# mic-preamp-stereo5.net
KiCad netlist of a schematic drawn in EAGLE
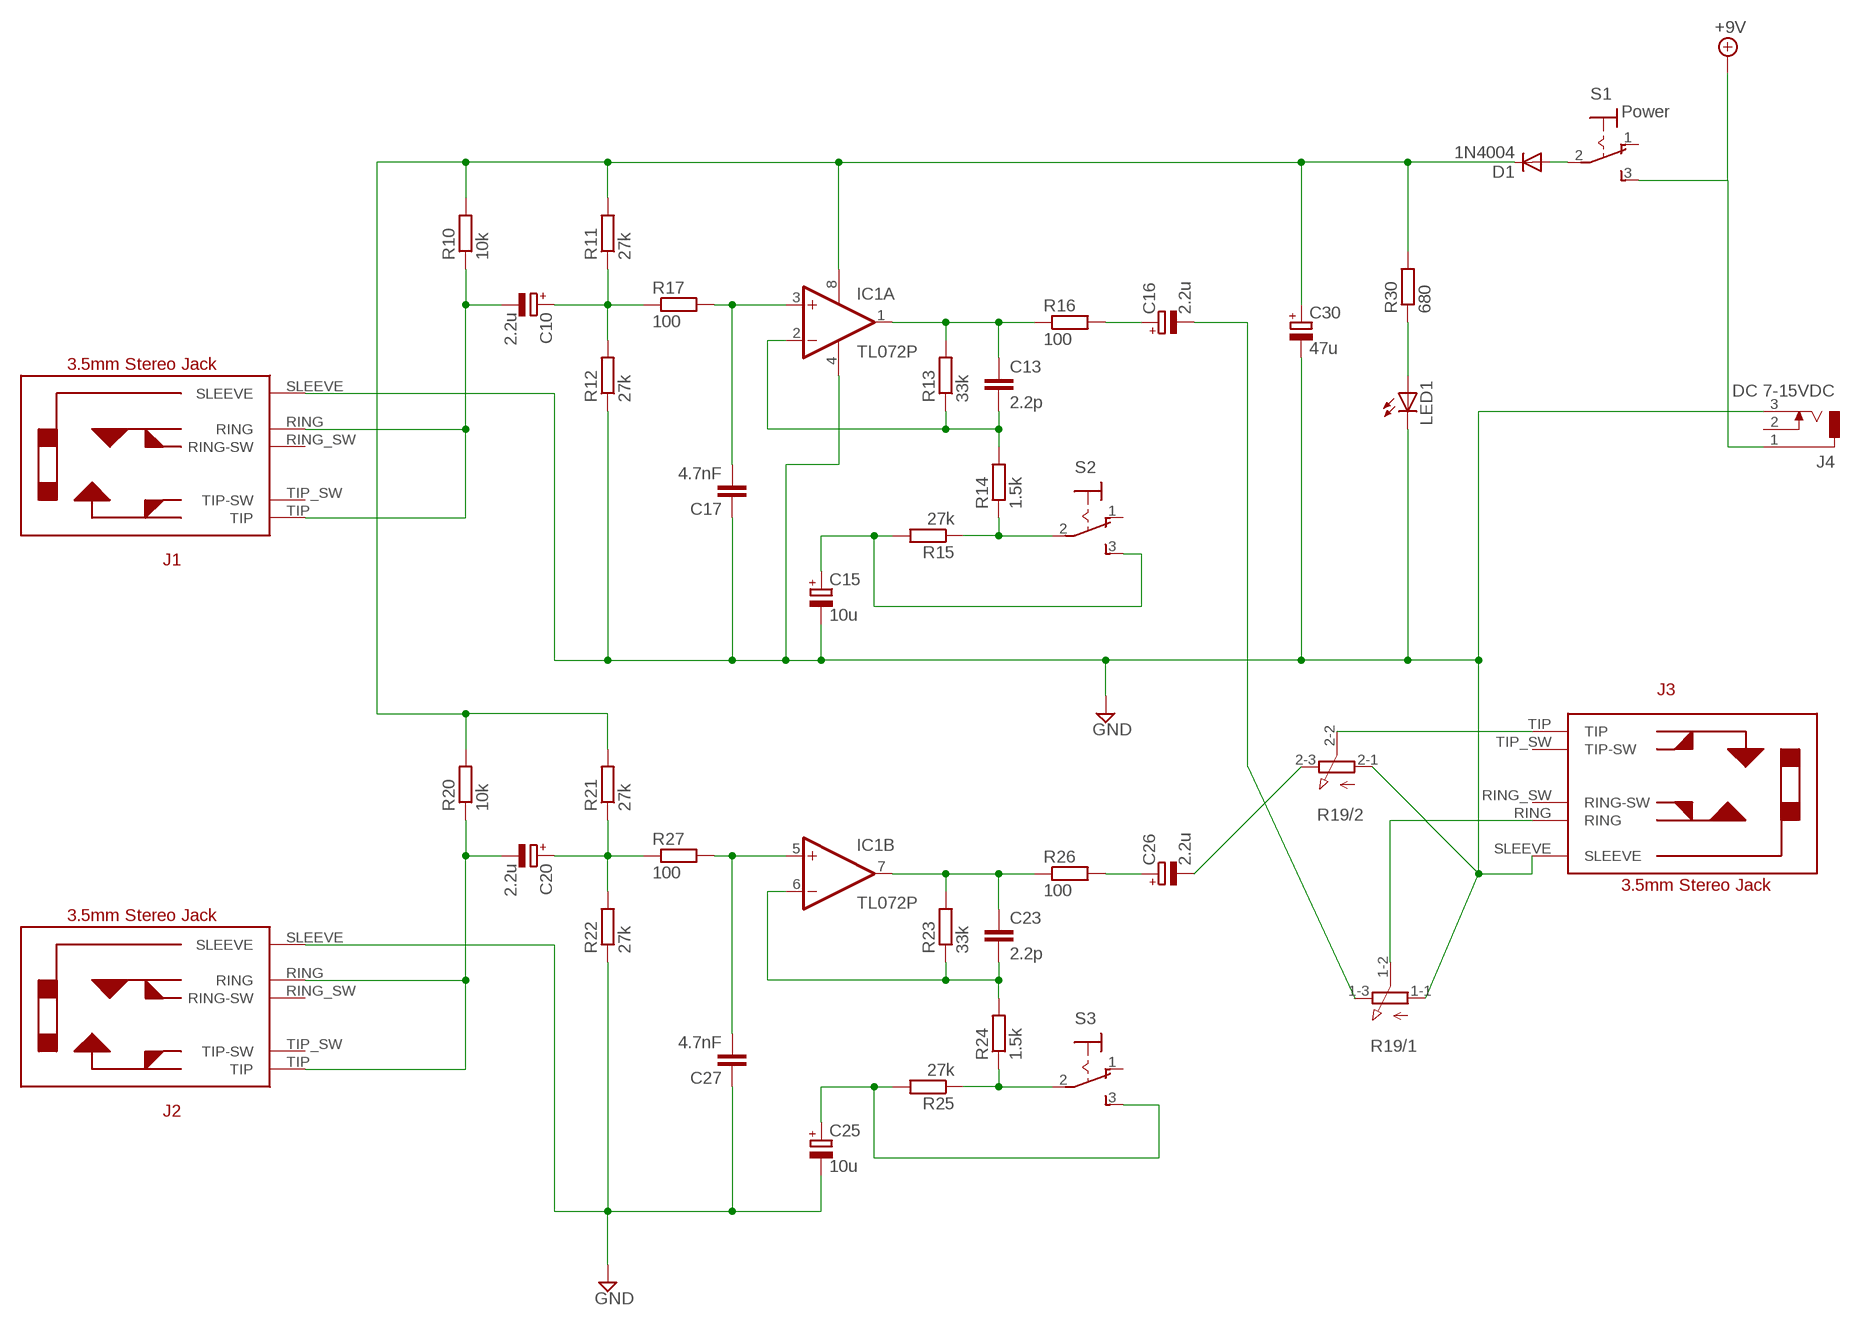
[diagram p0: schematic, sheet 1]

(export (version "E")
  (design (tool "Eeschema 10.0.6"))
  (components
    (comp (ref "C10")
      (value "2.2u")
      (footprint "eagle-import:E2-5")
      (libsource (lib "eagle-import") (part "CPOL-EUE2-5"))
    )
    (comp (ref "C13")
      (value "2.2p")
      (footprint "eagle-import:C025-024X044")
      (libsource (lib "eagle-import") (part "C-EU025-024X044"))
    )
    (comp (ref "C15")
      (value "10u")
      (footprint "eagle-import:E2-5")
      (libsource (lib "eagle-import") (part "CPOL-EUE2-5"))
    )
    (comp (ref "C16")
      (value "2.2u")
      (footprint "eagle-import:E2-5")
      (libsource (lib "eagle-import") (part "CPOL-EUE2-5"))
    )
    (comp (ref "C17")
      (value "4.7nF")
      (footprint "eagle-import:C025-024X044")
      (libsource (lib "eagle-import") (part "C-EU025-024X044"))
    )
    (comp (ref "C20")
      (value "2.2u")
      (footprint "eagle-import:E2-5")
      (libsource (lib "eagle-import") (part "CPOL-EUE2-5"))
    )
    (comp (ref "C23")
      (value "2.2p")
      (footprint "eagle-import:C025-024X044")
      (libsource (lib "eagle-import") (part "C-EU025-024X044"))
    )
    (comp (ref "C25")
      (value "10u")
      (footprint "eagle-import:E2-5")
      (libsource (lib "eagle-import") (part "CPOL-EUE2-5"))
    )
    (comp (ref "C26")
      (value "2.2u")
      (footprint "eagle-import:E2-5")
      (libsource (lib "eagle-import") (part "CPOL-EUE2-5"))
    )
    (comp (ref "C27")
      (value "4.7nF")
      (footprint "eagle-import:C025-024X044")
      (libsource (lib "eagle-import") (part "C-EU025-024X044"))
    )
    (comp (ref "C30")
      (value "47u")
      (footprint "eagle-import:E2-5")
      (libsource (lib "eagle-import") (part "CPOL-EUE2-5"))
    )
    (comp (ref "D1")
      (value "1N4004")
      (footprint "eagle-import:DO41-10")
      (libsource (lib "eagle-import") (part "1N4004"))
    )
    (comp (ref "IC1")
      (value "TL072P")
      (footprint "eagle-import:DIL08")
      (libsource (lib "eagle-import") (part "TL072P"))
    )
    (comp (ref "J1")
      (value "PICAXE_STEREOJACKSOCKET")
      (footprint "eagle-import:PICAXE_STEREOJACKSOCKET")
      (libsource (lib "eagle-import") (part "PICAXE_STEREOJACKSOCKET"))
    )
    (comp (ref "J2")
      (value "PICAXE_STEREOJACKSOCKET")
      (footprint "eagle-import:PICAXE_STEREOJACKSOCKET")
      (libsource (lib "eagle-import") (part "PICAXE_STEREOJACKSOCKET"))
    )
    (comp (ref "J3")
      (value "Stereo Out")
      (footprint "eagle-import:PICAXE_STEREOJACKSOCKET")
      (libsource (lib "eagle-import") (part "PICAXE_STEREOJACKSOCKET"))
    )
    (comp (ref "J4")
      (value "DC 7-15VDC")
      (footprint "eagle-import:DCJ0202")
      (libsource (lib "eagle-import") (part "DCJ0202"))
    )
    (comp (ref "LED1")
      (value "LED5MM")
      (footprint "eagle-import:LED5MM")
      (libsource (lib "eagle-import") (part "LED5MM"))
    )
    (comp (ref "R10")
      (value "10k")
      (footprint "eagle-import:0207_5V")
      (libsource (lib "eagle-import") (part "R-EU_0207/5V"))
    )
    (comp (ref "R11")
      (value "27k")
      (footprint "eagle-import:0207_5V")
      (libsource (lib "eagle-import") (part "R-EU_0207/5V"))
    )
    (comp (ref "R12")
      (value "27k")
      (footprint "eagle-import:0207_5V")
      (libsource (lib "eagle-import") (part "R-EU_0207/5V"))
    )
    (comp (ref "R13")
      (value "33k")
      (footprint "eagle-import:0207_5V")
      (libsource (lib "eagle-import") (part "R-EU_0207/5V"))
    )
    (comp (ref "R14")
      (value "1.5k")
      (footprint "eagle-import:0207_5V")
      (libsource (lib "eagle-import") (part "R-EU_0207/5V"))
    )
    (comp (ref "R15")
      (value "27k")
      (footprint "eagle-import:0207_5V")
      (libsource (lib "eagle-import") (part "R-EU_0207/5V"))
    )
    (comp (ref "R16")
      (value "100")
      (footprint "eagle-import:0207_5V")
      (libsource (lib "eagle-import") (part "R-EU_0207/5V"))
    )
    (comp (ref "R17")
      (value "100")
      (footprint "eagle-import:0207_5V")
      (libsource (lib "eagle-import") (part "resistor_R-EU_0207/5V"))
    )
    (comp (ref "R19")
      (value "3RP/1610G")
      (footprint "eagle-import:3RP_1610G")
      (libsource (lib "eagle-import") (part "3RP/1610G"))
    )
    (comp (ref "R20")
      (value "10k")
      (footprint "eagle-import:0207_5V")
      (libsource (lib "eagle-import") (part "R-EU_0207/5V"))
    )
    (comp (ref "R21")
      (value "27k")
      (footprint "eagle-import:0207_5V")
      (libsource (lib "eagle-import") (part "R-EU_0207/5V"))
    )
    (comp (ref "R22")
      (value "27k")
      (footprint "eagle-import:0207_5V")
      (libsource (lib "eagle-import") (part "R-EU_0207/5V"))
    )
    (comp (ref "R23")
      (value "33k")
      (footprint "eagle-import:0207_5V")
      (libsource (lib "eagle-import") (part "R-EU_0207/5V"))
    )
    (comp (ref "R24")
      (value "1.5k")
      (footprint "eagle-import:0207_5V")
      (libsource (lib "eagle-import") (part "R-EU_0207/5V"))
    )
    (comp (ref "R25")
      (value "27k")
      (footprint "eagle-import:0207_5V")
      (libsource (lib "eagle-import") (part "R-EU_0207/5V"))
    )
    (comp (ref "R26")
      (value "100")
      (footprint "eagle-import:0207_5V")
      (libsource (lib "eagle-import") (part "R-EU_0207/5V"))
    )
    (comp (ref "R27")
      (value "100")
      (footprint "eagle-import:0207_5V")
      (libsource (lib "eagle-import") (part "resistor_R-EU_0207/5V"))
    )
    (comp (ref "R30")
      (value "680")
      (footprint "eagle-import:0207_12")
      (libsource (lib "eagle-import") (part "R-EU_0207/12"))
    )
    (comp (ref "S1")
      (value "Power")
      (footprint "eagle-import:M9040P")
      (libsource (lib "eagle-import") (part "M9040P"))
    )
    (comp (ref "S2")
      (value "M9040P")
      (footprint "eagle-import:M9040P")
      (libsource (lib "eagle-import") (part "M9040P"))
    )
    (comp (ref "S3")
      (value "M9040P")
      (footprint "eagle-import:M9040P")
      (libsource (lib "eagle-import") (part "M9040P"))
    )
  )
  (nets
    (net (code "1") (name "+9V") (class "Default")
      (node (ref "J4") (pin "1") (pinfunction "1_1") (pintype "passive"))
      (node (ref "S1") (pin "3") (pinfunction "S_3") (pintype "passive"))
    )
    (net (code "2") (name "GND") (class "Default")
      (node (ref "C15") (pin "-") (pinfunction "-_-") (pintype "passive"))
      (node (ref "C17") (pin "1") (pinfunction "1_1") (pintype "passive"))
      (node (ref "C25") (pin "-") (pinfunction "-_-") (pintype "passive"))
      (node (ref "C27") (pin "1") (pinfunction "1_1") (pintype "passive"))
      (node (ref "C30") (pin "-") (pinfunction "-_-") (pintype "passive"))
      (node (ref "IC1") (pin "4") (pinfunction "V-_4") (pintype "power_in"))
      (node (ref "J1") (pin "SLEEVE") (pinfunction "SLEEVE_SLEEVE") (pintype "bidirectional"))
      (node (ref "J2") (pin "SLEEVE") (pinfunction "SLEEVE_SLEEVE") (pintype "bidirectional"))
      (node (ref "J3") (pin "SLEEVE") (pinfunction "SLEEVE_SLEEVE") (pintype "bidirectional"))
      (node (ref "J4") (pin "3") (pinfunction "3_3") (pintype "passive"))
      (node (ref "LED1") (pin "K") (pinfunction "C_K") (pintype "passive"))
      (node (ref "R12") (pin "1") (pinfunction "1_1") (pintype "passive"))
      (node (ref "R19") (pin "1-1") (pinfunction "A_1-1") (pintype "passive"))
      (node (ref "R19") (pin "2-1") (pinfunction "A_2-1") (pintype "passive"))
      (node (ref "R22") (pin "1") (pinfunction "1_1") (pintype "passive"))
    )
    (net (code "3") (name "Net-(C10-Pad+)") (class "Default")
      (node (ref "C10") (pin "+") (pinfunction "+_+") (pintype "passive"))
      (node (ref "R11") (pin "1") (pinfunction "1_1") (pintype "passive"))
      (node (ref "R12") (pin "2") (pinfunction "2_2") (pintype "passive"))
      (node (ref "R17") (pin "1") (pinfunction "1_1") (pintype "passive"))
    )
    (net (code "4") (name "Net-(C10-Pad-)") (class "Default")
      (node (ref "C10") (pin "-") (pinfunction "-_-") (pintype "passive"))
      (node (ref "J1") (pin "RING") (pinfunction "RING_RING") (pintype "bidirectional"))
      (node (ref "J1") (pin "TIP") (pinfunction "TIP_TIP") (pintype "bidirectional"))
      (node (ref "R10") (pin "1") (pinfunction "1_1") (pintype "passive"))
    )
    (net (code "5") (name "Net-(C16-Pad+)") (class "Default")
      (node (ref "C16") (pin "+") (pinfunction "+_+") (pintype "passive"))
      (node (ref "R16") (pin "2") (pinfunction "2_2") (pintype "passive"))
    )
    (net (code "6") (name "Net-(C20-Pad+)") (class "Default")
      (node (ref "C20") (pin "+") (pinfunction "+_+") (pintype "passive"))
      (node (ref "R21") (pin "1") (pinfunction "1_1") (pintype "passive"))
      (node (ref "R22") (pin "2") (pinfunction "2_2") (pintype "passive"))
      (node (ref "R27") (pin "1") (pinfunction "1_1") (pintype "passive"))
    )
    (net (code "7") (name "Net-(C20-Pad-)") (class "Default")
      (node (ref "C20") (pin "-") (pinfunction "-_-") (pintype "passive"))
      (node (ref "J2") (pin "RING") (pinfunction "RING_RING") (pintype "bidirectional"))
      (node (ref "J2") (pin "TIP") (pinfunction "TIP_TIP") (pintype "bidirectional"))
      (node (ref "R20") (pin "1") (pinfunction "1_1") (pintype "passive"))
    )
    (net (code "8") (name "Net-(C26-Pad+)") (class "Default")
      (node (ref "C26") (pin "+") (pinfunction "+_+") (pintype "passive"))
      (node (ref "R26") (pin "2") (pinfunction "2_2") (pintype "passive"))
    )
    (net (code "9") (name "Net-(IC1A-+IN)") (class "Default")
      (node (ref "C17") (pin "2") (pinfunction "2_2") (pintype "passive"))
      (node (ref "IC1") (pin "3") (pinfunction "+IN_3") (pintype "input"))
      (node (ref "R17") (pin "2") (pinfunction "2_2") (pintype "passive"))
    )
    (net (code "10") (name "Net-(IC1A--IN)") (class "Default")
      (node (ref "C13") (pin "2") (pinfunction "2_2") (pintype "passive"))
      (node (ref "IC1") (pin "2") (pinfunction "-IN_2") (pintype "input"))
      (node (ref "R13") (pin "1") (pinfunction "1_1") (pintype "passive"))
      (node (ref "R14") (pin "2") (pinfunction "2_2") (pintype "passive"))
    )
    (net (code "11") (name "Net-(IC1A-OUT)") (class "Default")
      (node (ref "C13") (pin "1") (pinfunction "1_1") (pintype "passive"))
      (node (ref "IC1") (pin "1") (pinfunction "OUT_1") (pintype "output"))
      (node (ref "R13") (pin "2") (pinfunction "2_2") (pintype "passive"))
      (node (ref "R16") (pin "1") (pinfunction "1_1") (pintype "passive"))
    )
    (net (code "12") (name "Net-(IC1B-+IN)") (class "Default")
      (node (ref "C27") (pin "2") (pinfunction "2_2") (pintype "passive"))
      (node (ref "IC1") (pin "5") (pinfunction "+IN_5") (pintype "input"))
      (node (ref "R27") (pin "2") (pinfunction "2_2") (pintype "passive"))
    )
    (net (code "13") (name "Net-(IC1B--IN)") (class "Default")
      (node (ref "C23") (pin "2") (pinfunction "2_2") (pintype "passive"))
      (node (ref "IC1") (pin "6") (pinfunction "-IN_6") (pintype "input"))
      (node (ref "R23") (pin "1") (pinfunction "1_1") (pintype "passive"))
      (node (ref "R24") (pin "2") (pinfunction "2_2") (pintype "passive"))
    )
    (net (code "14") (name "Net-(IC1B-OUT)") (class "Default")
      (node (ref "C23") (pin "1") (pinfunction "1_1") (pintype "passive"))
      (node (ref "IC1") (pin "7") (pinfunction "OUT_7") (pintype "output"))
      (node (ref "R23") (pin "2") (pinfunction "2_2") (pintype "passive"))
      (node (ref "R26") (pin "1") (pinfunction "1_1") (pintype "passive"))
    )
    (net (code "15") (name "Net-(IC1C-V+)") (class "Default")
      (node (ref "C30") (pin "+") (pinfunction "+_+") (pintype "passive"))
      (node (ref "D1") (pin "C") (pinfunction "C_C") (pintype "passive"))
      (node (ref "IC1") (pin "8") (pinfunction "V+_8") (pintype "power_in"))
      (node (ref "R10") (pin "2") (pinfunction "2_2") (pintype "passive"))
      (node (ref "R11") (pin "2") (pinfunction "2_2") (pintype "passive"))
      (node (ref "R20") (pin "2") (pinfunction "2_2") (pintype "passive"))
      (node (ref "R21") (pin "2") (pinfunction "2_2") (pintype "passive"))
      (node (ref "R30") (pin "2") (pinfunction "2_2") (pintype "passive"))
    )
    (net (code "16") (name "Net-(LED1-PadA)") (class "Default")
      (node (ref "LED1") (pin "A") (pinfunction "A_A") (pintype "passive"))
      (node (ref "R30") (pin "1") (pinfunction "1_1") (pintype "passive"))
    )
    (net (code "17") (name "Net-(R19A-E)") (class "Default")
      (node (ref "C16") (pin "-") (pinfunction "-_-") (pintype "passive"))
      (node (ref "R19") (pin "1-3") (pinfunction "E_1-3") (pintype "passive"))
    )
    (net (code "18") (name "Net-(R19A-S)") (class "Default")
      (node (ref "J3") (pin "RING") (pinfunction "RING_RING") (pintype "bidirectional"))
      (node (ref "R19") (pin "1-2") (pinfunction "S_1-2") (pintype "passive"))
    )
    (net (code "19") (name "Net-(R19B-E)") (class "Default")
      (node (ref "C26") (pin "-") (pinfunction "-_-") (pintype "passive"))
      (node (ref "R19") (pin "2-3") (pinfunction "E_2-3") (pintype "passive"))
    )
    (net (code "20") (name "Net-(R19B-S)") (class "Default")
      (node (ref "J3") (pin "TIP") (pinfunction "TIP_TIP") (pintype "bidirectional"))
      (node (ref "R19") (pin "2-2") (pinfunction "S_2-2") (pintype "passive"))
    )
    (net (code "21") (name "Net-(S1-P)") (class "Default")
      (node (ref "D1") (pin "A") (pinfunction "A_A") (pintype "passive"))
      (node (ref "S1") (pin "2") (pinfunction "P_2") (pintype "passive"))
    )
    (net (code "22") (name "Net-(S2-P)") (class "Default")
      (node (ref "R14") (pin "1") (pinfunction "1_1") (pintype "passive"))
      (node (ref "R15") (pin "1") (pinfunction "1_1") (pintype "passive"))
      (node (ref "S2") (pin "2") (pinfunction "P_2") (pintype "passive"))
    )
    (net (code "23") (name "Net-(S2-S)") (class "Default")
      (node (ref "C15") (pin "+") (pinfunction "+_+") (pintype "passive"))
      (node (ref "R15") (pin "2") (pinfunction "2_2") (pintype "passive"))
      (node (ref "S2") (pin "3") (pinfunction "S_3") (pintype "passive"))
    )
    (net (code "24") (name "Net-(S3-P)") (class "Default")
      (node (ref "R24") (pin "1") (pinfunction "1_1") (pintype "passive"))
      (node (ref "R25") (pin "1") (pinfunction "1_1") (pintype "passive"))
      (node (ref "S3") (pin "2") (pinfunction "P_2") (pintype "passive"))
    )
    (net (code "25") (name "Net-(S3-S)") (class "Default")
      (node (ref "C25") (pin "+") (pinfunction "+_+") (pintype "passive"))
      (node (ref "R25") (pin "2") (pinfunction "2_2") (pintype "passive"))
      (node (ref "S3") (pin "3") (pinfunction "S_3") (pintype "passive"))
    )
    (net (code "26") (name "unconnected-(J1-RING-SW-PadRING_SW)") (class "Default")
      (node (ref "J1") (pin "RING_SW") (pinfunction "RING-SW_RING_SW") (pintype "bidirectional"))
    )
    (net (code "27") (name "unconnected-(J1-TIP-SW-PadTIP_SW)") (class "Default")
      (node (ref "J1") (pin "TIP_SW") (pinfunction "TIP-SW_TIP_SW") (pintype "bidirectional"))
    )
    (net (code "28") (name "unconnected-(J2-RING-SW-PadRING_SW)") (class "Default")
      (node (ref "J2") (pin "RING_SW") (pinfunction "RING-SW_RING_SW") (pintype "bidirectional"))
    )
    (net (code "29") (name "unconnected-(J2-TIP-SW-PadTIP_SW)") (class "Default")
      (node (ref "J2") (pin "TIP_SW") (pinfunction "TIP-SW_TIP_SW") (pintype "bidirectional"))
    )
    (net (code "30") (name "unconnected-(J3-RING-SW-PadRING_SW)") (class "Default")
      (node (ref "J3") (pin "RING_SW") (pinfunction "RING-SW_RING_SW") (pintype "bidirectional"))
    )
    (net (code "31") (name "unconnected-(J3-TIP-SW-PadTIP_SW)") (class "Default")
      (node (ref "J3") (pin "TIP_SW") (pinfunction "TIP-SW_TIP_SW") (pintype "bidirectional"))
    )
    (net (code "32") (name "unconnected-(J4-Pad2)") (class "Default")
      (node (ref "J4") (pin "2") (pinfunction "2_2") (pintype "passive"))
    )
    (net (code "33") (name "unconnected-(S1-O-Pad1)") (class "Default")
      (node (ref "S1") (pin "1") (pinfunction "O_1") (pintype "passive"))
    )
    (net (code "34") (name "unconnected-(S2-O-Pad1)") (class "Default")
      (node (ref "S2") (pin "1") (pinfunction "O_1") (pintype "passive"))
    )
    (net (code "35") (name "unconnected-(S3-O-Pad1)") (class "Default")
      (node (ref "S3") (pin "1") (pinfunction "O_1") (pintype "passive"))
    )
  )
)
